# avrboard.net
KiCad netlist of a schematic drawn in EAGLE
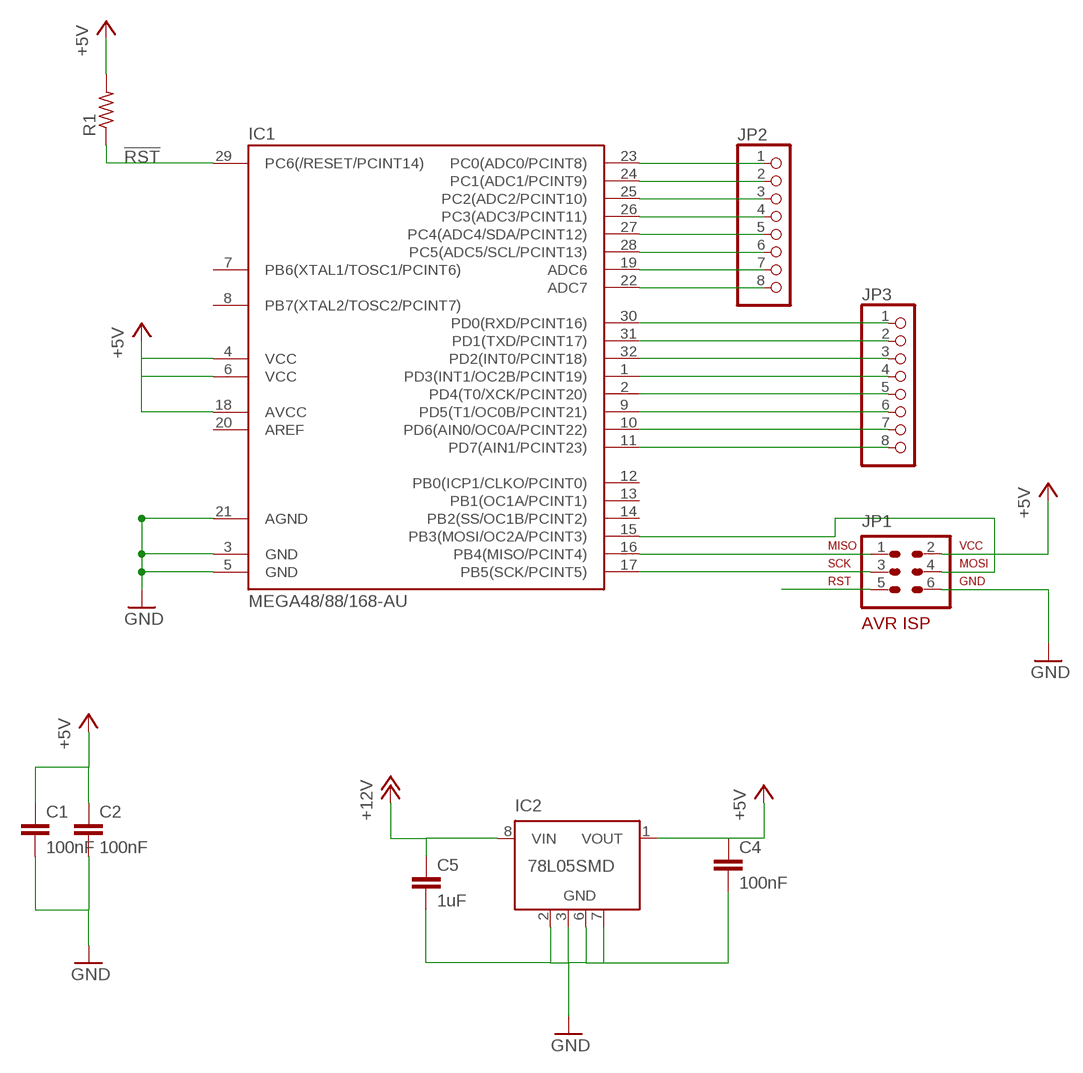
[diagram p0: schematic, sheet 1]

(export (version "E")
  (design (tool "Eeschema 10.0.6"))
  (components
    (comp (ref "C1")
      (value "100nF")
      (footprint "eagle-import:C0805")
      (libsource (lib "eagle-import") (part "C-EUC0805"))
    )
    (comp (ref "C2")
      (value "100nF")
      (footprint "eagle-import:C0805")
      (libsource (lib "eagle-import") (part "C-EUC0805"))
    )
    (comp (ref "C4")
      (value "100nF")
      (footprint "eagle-import:C0805")
      (libsource (lib "eagle-import") (part "C-EUC0805"))
    )
    (comp (ref "C5")
      (value "1uF")
      (footprint "eagle-import:C0805")
      (libsource (lib "eagle-import") (part "C-EUC0805"))
    )
    (comp (ref "IC1")
      (value "MEGA48/88/168-AU")
      (footprint "eagle-import:TQFP32-08")
      (libsource (lib "eagle-import") (part "MEGA48/88/168-AU"))
    )
    (comp (ref "IC2")
      (value "78L05SMD")
      (footprint "eagle-import:SO08")
      (libsource (lib "eagle-import") (part "78LSMD05"))
    )
    (comp (ref "JP1")
      (value "AVR-ISP-6VERT")
      (footprint "eagle-import:AVR-ISP-6")
      (libsource (lib "eagle-import") (part "AVR-ISP-6VERT"))
    )
    (comp (ref "JP2")
      (value "PINHD-1X8")
      (footprint "eagle-import:1X08")
      (libsource (lib "eagle-import") (part "PINHD-1X8"))
    )
    (comp (ref "JP3")
      (value "PINHD-1X8")
      (footprint "eagle-import:1X08")
      (libsource (lib "eagle-import") (part "PINHD-1X8"))
    )
    (comp (ref "R1")
      (value "R-US_R0805")
      (footprint "eagle-import:R0805")
      (libsource (lib "eagle-import") (part "R-US_R0805"))
    )
  )
  (nets
    (net (code "1") (name "+5V") (class "Default")
      (node (ref "C1") (pin "1") (pinfunction "1_1") (pintype "passive"))
      (node (ref "C2") (pin "1") (pinfunction "1_1") (pintype "passive"))
      (node (ref "C4") (pin "1") (pinfunction "1_1") (pintype "passive"))
      (node (ref "IC1") (pin "18") (pinfunction "AVCC_18") (pintype "passive"))
      (node (ref "IC1") (pin "4") (pinfunction "VCC_4") (pintype "power_in"))
      (node (ref "IC1") (pin "6") (pinfunction "VCC_6") (pintype "power_in"))
      (node (ref "IC2") (pin "1") (pinfunction "VOUT_1") (pintype "output"))
      (node (ref "JP1") (pin "2") (pinfunction "2_2") (pintype "passive"))
      (node (ref "R1") (pin "2") (pinfunction "2_2") (pintype "passive"))
    )
    (net (code "2") (name "+12V") (class "Default")
      (node (ref "C5") (pin "1") (pinfunction "1_1") (pintype "passive"))
      (node (ref "IC2") (pin "8") (pinfunction "VIN_8") (pintype "passive"))
    )
    (net (code "3") (name "/~{RST}") (class "Default")
      (node (ref "IC1") (pin "29") (pinfunction "PC6(/RESET/PCINT14)_29") (pintype "bidirectional"))
      (node (ref "JP1") (pin "5") (pinfunction "5_5") (pintype "passive"))
      (node (ref "R1") (pin "1") (pinfunction "1_1") (pintype "passive"))
    )
    (net (code "4") (name "GND") (class "Default")
      (node (ref "C1") (pin "2") (pinfunction "2_2") (pintype "passive"))
      (node (ref "C2") (pin "2") (pinfunction "2_2") (pintype "passive"))
      (node (ref "C4") (pin "2") (pinfunction "2_2") (pintype "passive"))
      (node (ref "C5") (pin "2") (pinfunction "2_2") (pintype "passive"))
      (node (ref "IC1") (pin "21") (pinfunction "AGND_21") (pintype "power_in"))
      (node (ref "IC1") (pin "3") (pinfunction "GND_3") (pintype "power_in"))
      (node (ref "IC1") (pin "5") (pinfunction "GND_5") (pintype "power_in"))
      (node (ref "IC2") (pin "2") (pinfunction "GND_2") (pintype "power_in"))
      (node (ref "IC2") (pin "3") (pinfunction "GND_3") (pintype "power_in"))
      (node (ref "IC2") (pin "6") (pinfunction "GND_6") (pintype "power_in"))
      (node (ref "IC2") (pin "7") (pinfunction "GND_7") (pintype "power_in"))
      (node (ref "JP1") (pin "6") (pinfunction "6_6") (pintype "passive"))
    )
    (net (code "5") (name "Net-(IC1-ADC6)") (class "Default")
      (node (ref "IC1") (pin "19") (pinfunction "ADC6_19") (pintype "passive"))
      (node (ref "JP2") (pin "7") (pinfunction "7_7") (pintype "passive"))
    )
    (net (code "6") (name "Net-(IC1-ADC7)") (class "Default")
      (node (ref "IC1") (pin "22") (pinfunction "ADC7_22") (pintype "passive"))
      (node (ref "JP2") (pin "8") (pinfunction "8_8") (pintype "passive"))
    )
    (net (code "7") (name "Net-(IC1-PB3(MOSI{slash}OC2A{slash}PCINT3))") (class "Default")
      (node (ref "IC1") (pin "15") (pinfunction "PB3(MOSI/OC2A/PCINT3)_15") (pintype "bidirectional"))
      (node (ref "JP1") (pin "4") (pinfunction "4_4") (pintype "passive"))
    )
    (net (code "8") (name "Net-(IC1-PB4(MISO{slash}PCINT4))") (class "Default")
      (node (ref "IC1") (pin "16") (pinfunction "PB4(MISO/PCINT4)_16") (pintype "bidirectional"))
      (node (ref "JP1") (pin "1") (pinfunction "1_1") (pintype "passive"))
    )
    (net (code "9") (name "Net-(IC1-PB5(SCK{slash}PCINT5))") (class "Default")
      (node (ref "IC1") (pin "17") (pinfunction "PB5(SCK/PCINT5)_17") (pintype "bidirectional"))
      (node (ref "JP1") (pin "3") (pinfunction "3_3") (pintype "passive"))
    )
    (net (code "10") (name "Net-(IC1-PC0(ADC0{slash}PCINT8))") (class "Default")
      (node (ref "IC1") (pin "23") (pinfunction "PC0(ADC0/PCINT8)_23") (pintype "bidirectional"))
      (node (ref "JP2") (pin "1") (pinfunction "1_1") (pintype "passive"))
    )
    (net (code "11") (name "Net-(IC1-PC1(ADC1{slash}PCINT9))") (class "Default")
      (node (ref "IC1") (pin "24") (pinfunction "PC1(ADC1/PCINT9)_24") (pintype "bidirectional"))
      (node (ref "JP2") (pin "2") (pinfunction "2_2") (pintype "passive"))
    )
    (net (code "12") (name "Net-(IC1-PC2(ADC2{slash}PCINT10))") (class "Default")
      (node (ref "IC1") (pin "25") (pinfunction "PC2(ADC2/PCINT10)_25") (pintype "bidirectional"))
      (node (ref "JP2") (pin "3") (pinfunction "3_3") (pintype "passive"))
    )
    (net (code "13") (name "Net-(IC1-PC3(ADC3{slash}PCINT11))") (class "Default")
      (node (ref "IC1") (pin "26") (pinfunction "PC3(ADC3/PCINT11)_26") (pintype "bidirectional"))
      (node (ref "JP2") (pin "4") (pinfunction "4_4") (pintype "passive"))
    )
    (net (code "14") (name "Net-(IC1-PC4(ADC4{slash}SDA{slash}PCINT12))") (class "Default")
      (node (ref "IC1") (pin "27") (pinfunction "PC4(ADC4/SDA/PCINT12)_27") (pintype "bidirectional"))
      (node (ref "JP2") (pin "5") (pinfunction "5_5") (pintype "passive"))
    )
    (net (code "15") (name "Net-(IC1-PC5(ADC5{slash}SCL{slash}PCINT13))") (class "Default")
      (node (ref "IC1") (pin "28") (pinfunction "PC5(ADC5/SCL/PCINT13)_28") (pintype "bidirectional"))
      (node (ref "JP2") (pin "6") (pinfunction "6_6") (pintype "passive"))
    )
    (net (code "16") (name "Net-(IC1-PD0(RXD{slash}PCINT16))") (class "Default")
      (node (ref "IC1") (pin "30") (pinfunction "PD0(RXD/PCINT16)_30") (pintype "bidirectional"))
      (node (ref "JP3") (pin "1") (pinfunction "1_1") (pintype "passive"))
    )
    (net (code "17") (name "Net-(IC1-PD1(TXD{slash}PCINT17))") (class "Default")
      (node (ref "IC1") (pin "31") (pinfunction "PD1(TXD/PCINT17)_31") (pintype "bidirectional"))
      (node (ref "JP3") (pin "2") (pinfunction "2_2") (pintype "passive"))
    )
    (net (code "18") (name "Net-(IC1-PD2(INT0{slash}PCINT18))") (class "Default")
      (node (ref "IC1") (pin "32") (pinfunction "PD2(INT0/PCINT18)_32") (pintype "bidirectional"))
      (node (ref "JP3") (pin "3") (pinfunction "3_3") (pintype "passive"))
    )
    (net (code "19") (name "Net-(IC1-PD3(INT1{slash}OC2B{slash}PCINT19))") (class "Default")
      (node (ref "IC1") (pin "1") (pinfunction "PD3(INT1/OC2B/PCINT19)_1") (pintype "bidirectional"))
      (node (ref "JP3") (pin "4") (pinfunction "4_4") (pintype "passive"))
    )
    (net (code "20") (name "Net-(IC1-PD4(T0{slash}XCK{slash}PCINT20))") (class "Default")
      (node (ref "IC1") (pin "2") (pinfunction "PD4(T0/XCK/PCINT20)_2") (pintype "bidirectional"))
      (node (ref "JP3") (pin "5") (pinfunction "5_5") (pintype "passive"))
    )
    (net (code "21") (name "Net-(IC1-PD5(T1{slash}OC0B{slash}PCINT21))") (class "Default")
      (node (ref "IC1") (pin "9") (pinfunction "PD5(T1/OC0B/PCINT21)_9") (pintype "bidirectional"))
      (node (ref "JP3") (pin "6") (pinfunction "6_6") (pintype "passive"))
    )
    (net (code "22") (name "Net-(IC1-PD6(AIN0{slash}OC0A{slash}PCINT22))") (class "Default")
      (node (ref "IC1") (pin "10") (pinfunction "PD6(AIN0/OC0A/PCINT22)_10") (pintype "bidirectional"))
      (node (ref "JP3") (pin "7") (pinfunction "7_7") (pintype "passive"))
    )
    (net (code "23") (name "Net-(IC1-PD7(AIN1{slash}PCINT23))") (class "Default")
      (node (ref "IC1") (pin "11") (pinfunction "PD7(AIN1/PCINT23)_11") (pintype "bidirectional"))
      (node (ref "JP3") (pin "8") (pinfunction "8_8") (pintype "passive"))
    )
    (net (code "24") (name "unconnected-(IC1-AREF-Pad20)") (class "Default")
      (node (ref "IC1") (pin "20") (pinfunction "AREF_20") (pintype "passive"))
    )
    (net (code "25") (name "unconnected-(IC1-PB0(ICP1{slash}CLKO{slash}PCINT0)-Pad12)") (class "Default")
      (node (ref "IC1") (pin "12") (pinfunction "PB0(ICP1/CLKO/PCINT0)_12") (pintype "bidirectional"))
    )
    (net (code "26") (name "unconnected-(IC1-PB1(OC1A{slash}PCINT1)-Pad13)") (class "Default")
      (node (ref "IC1") (pin "13") (pinfunction "PB1(OC1A/PCINT1)_13") (pintype "bidirectional"))
    )
    (net (code "27") (name "unconnected-(IC1-PB2(SS{slash}OC1B{slash}PCINT2)-Pad14)") (class "Default")
      (node (ref "IC1") (pin "14") (pinfunction "PB2(SS/OC1B/PCINT2)_14") (pintype "bidirectional"))
    )
    (net (code "28") (name "unconnected-(IC1-PB6(XTAL1{slash}TOSC1{slash}PCINT6)-Pad7)") (class "Default")
      (node (ref "IC1") (pin "7") (pinfunction "PB6(XTAL1/TOSC1/PCINT6)_7") (pintype "bidirectional"))
    )
    (net (code "29") (name "unconnected-(IC1-PB7(XTAL2{slash}TOSC2{slash}PCINT7)-Pad8)") (class "Default")
      (node (ref "IC1") (pin "8") (pinfunction "PB7(XTAL2/TOSC2/PCINT7)_8") (pintype "bidirectional"))
    )
  )
)
